# VIC20_HypExp.net
KiCad netlist of a schematic drawn in EAGLE
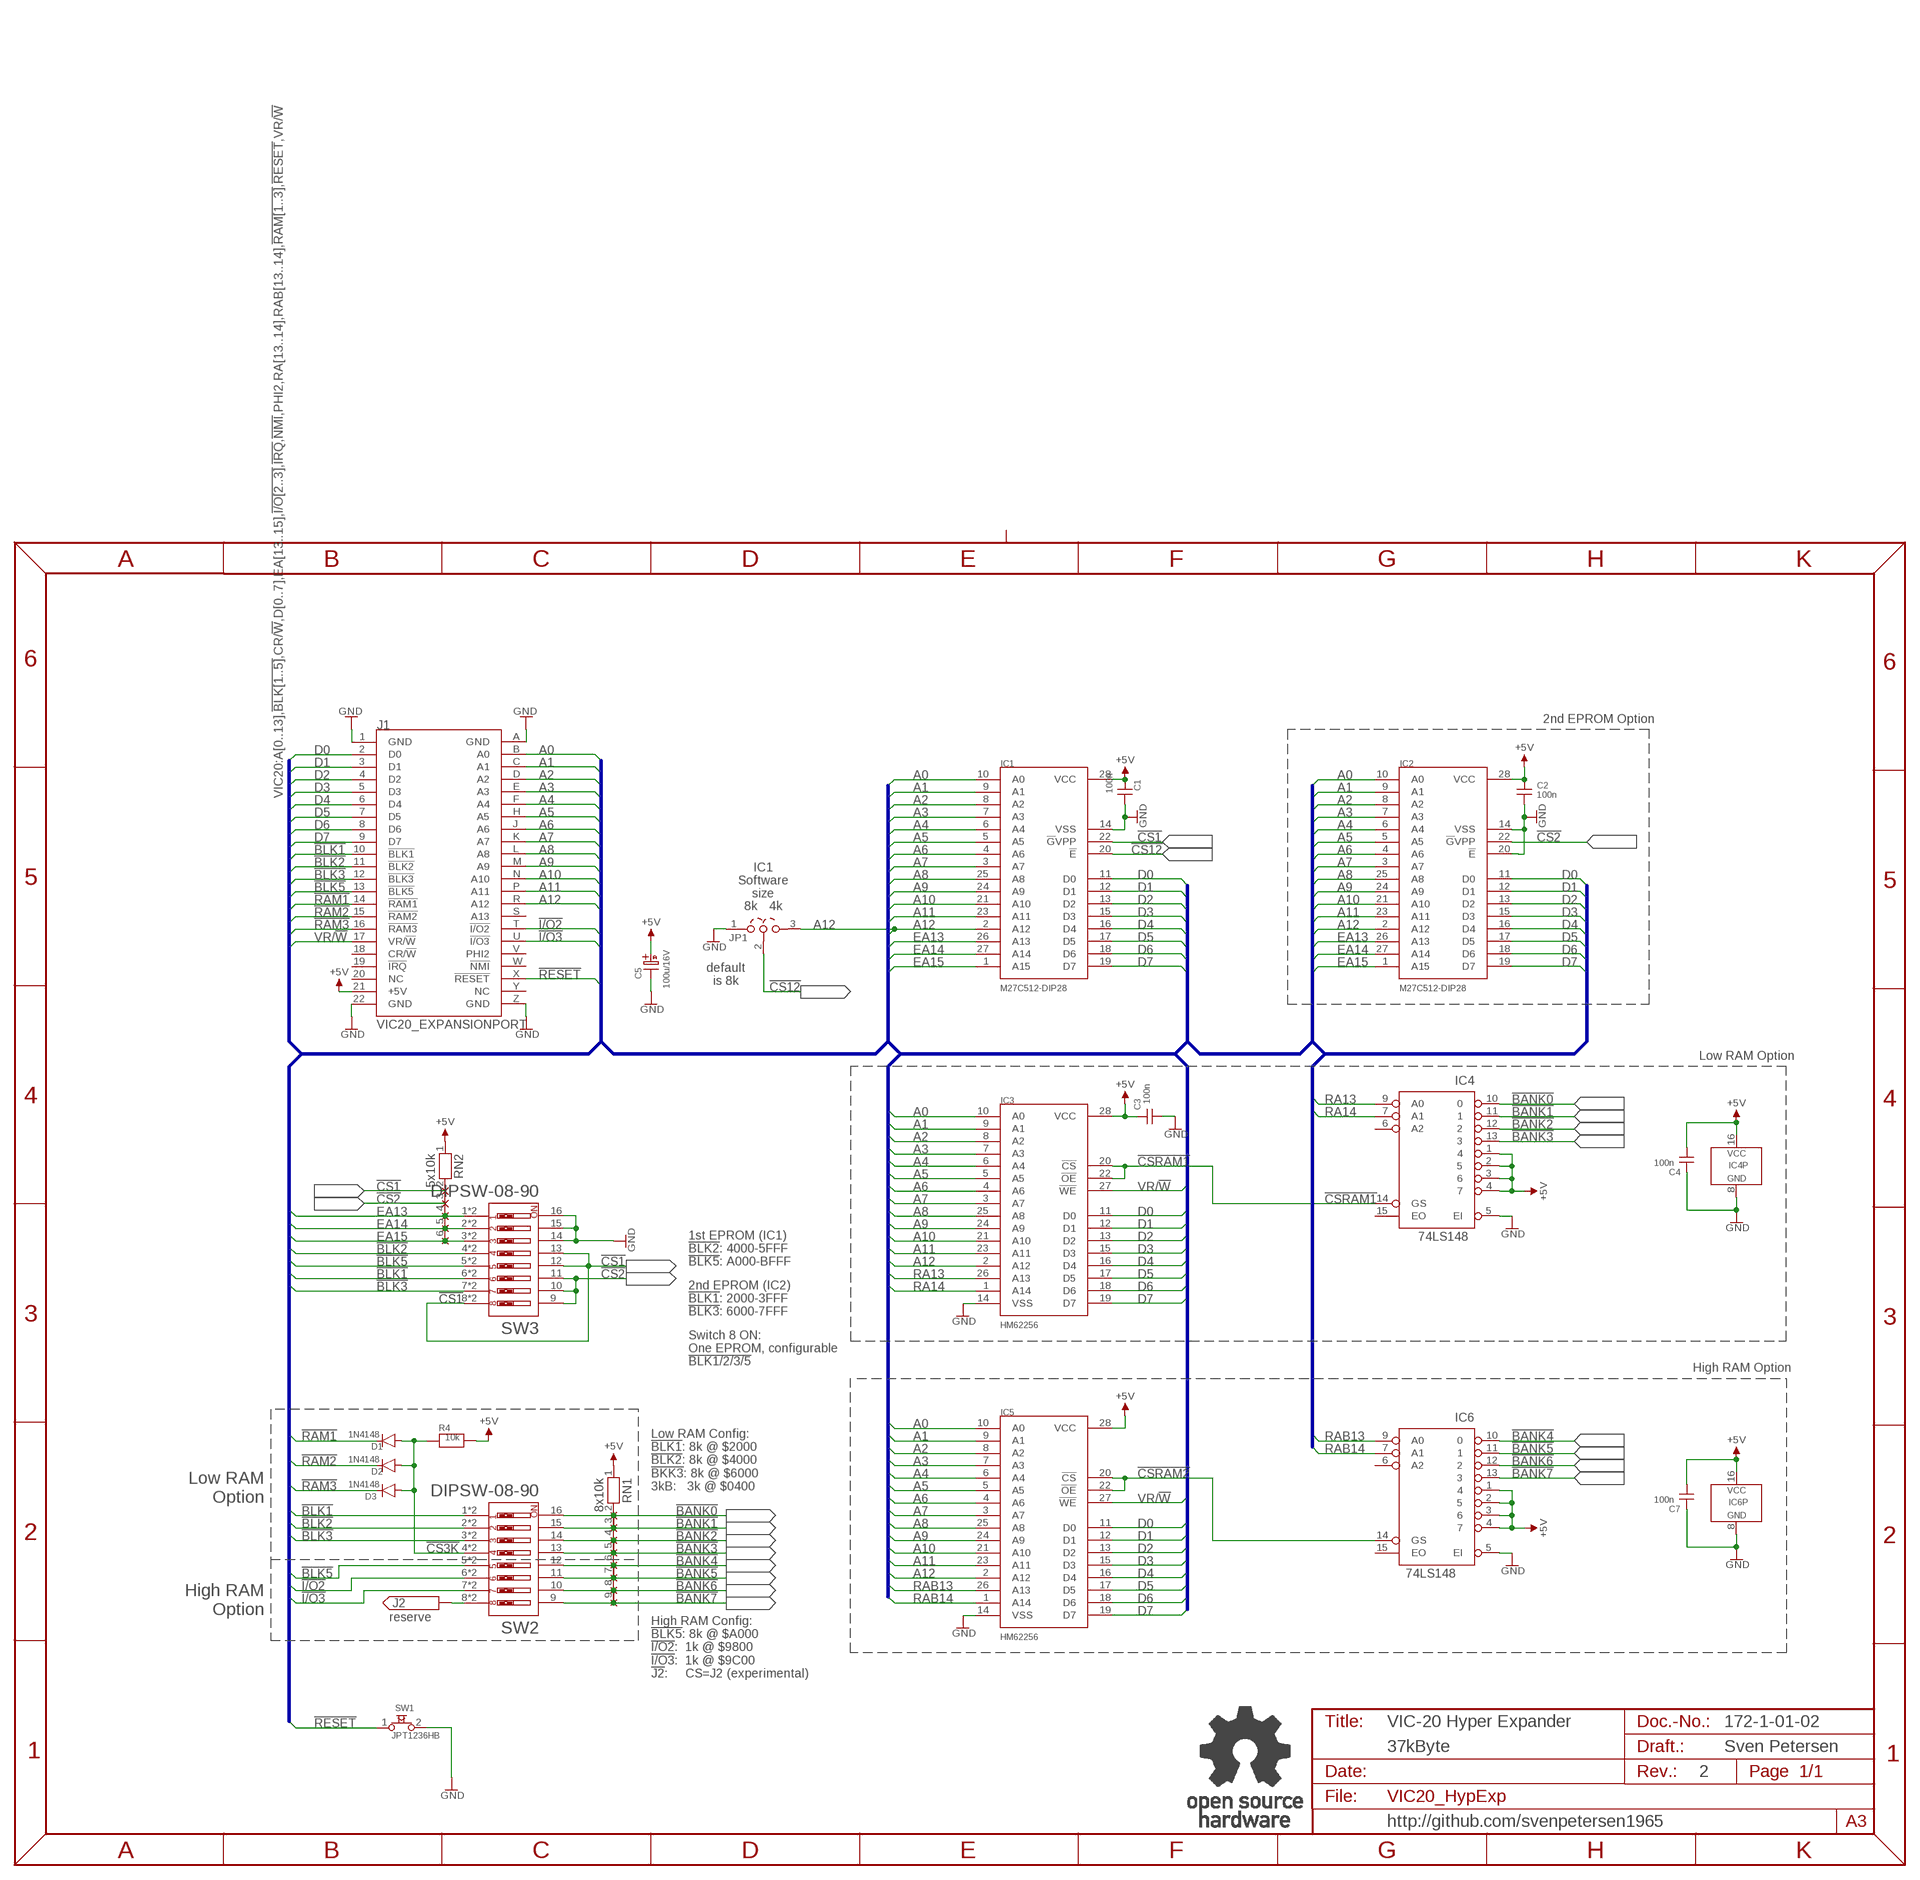
[diagram p0: schematic, sheet 1]

(export (version "E")
  (design (tool "Eeschema 10.0.6"))
  (components
    (comp (ref "C1")
      (value "100n")
      (footprint "eagle-import:C-2,5")
      (libsource (lib "eagle-import") (part "CAP01"))
    )
    (comp (ref "C2")
      (value "100n")
      (footprint "eagle-import:C-2,5")
      (libsource (lib "eagle-import") (part "CAP01"))
    )
    (comp (ref "C3")
      (value "100n")
      (footprint "eagle-import:C-2,5")
      (libsource (lib "eagle-import") (part "CAP01"))
    )
    (comp (ref "C4")
      (value "100n")
      (footprint "eagle-import:C-2,5")
      (libsource (lib "eagle-import") (part "CAP01"))
    )
    (comp (ref "C5")
      (value "100u/16V")
      (footprint "eagle-import:C07_2,5")
      (libsource (lib "eagle-import") (part "C07/2,5"))
    )
    (comp (ref "C7")
      (value "100n")
      (footprint "eagle-import:C-2,5")
      (libsource (lib "eagle-import") (part "CAP01"))
    )
    (comp (ref "D1")
      (value "1N4148")
      (footprint "eagle-import:DO-35_3")
      (libsource (lib "eagle-import") (part "1N41480.3{dblquote}"))
    )
    (comp (ref "D2")
      (value "1N4148")
      (footprint "eagle-import:DO-35_3")
      (libsource (lib "eagle-import") (part "1N41480.3{dblquote}"))
    )
    (comp (ref "D3")
      (value "1N4148")
      (footprint "eagle-import:DO-35_3")
      (libsource (lib "eagle-import") (part "1N41480.3{dblquote}"))
    )
    (comp (ref "IC1")
      (value "M27C512-DIP28")
      (footprint "eagle-import:DIL28-6")
      (libsource (lib "eagle-import") (part "M27C512-DIP28"))
    )
    (comp (ref "IC2")
      (value "M27C512-DIP28")
      (footprint "eagle-import:DIL28-6")
      (libsource (lib "eagle-import") (part "M27C512-DIP28"))
    )
    (comp (ref "IC3")
      (value "HM62256")
      (footprint "eagle-import:DIL28-6")
      (libsource (lib "eagle-import") (part "HM62256"))
    )
    (comp (ref "IC4")
      (value "74LS148")
      (footprint "eagle-import:DIL-16")
      (libsource (lib "eagle-import") (part "74148DIL"))
    )
    (comp (ref "IC5")
      (value "HM62256")
      (footprint "eagle-import:DIL28-6")
      (libsource (lib "eagle-import") (part "HM62256"))
    )
    (comp (ref "IC6")
      (value "74LS148")
      (footprint "eagle-import:DIL-16")
      (libsource (lib "eagle-import") (part "74148DIL"))
    )
    (comp (ref "J1")
      (value "VIC20_EXPANSIONPORT")
      (footprint "eagle-import:VIC20_EXPANSION")
      (libsource (lib "eagle-import") (part "VIC20_EXPANSIONPORT"))
    )
    (comp (ref "J2")
      (value "PINHD-1X1")
      (footprint "eagle-import:1X01")
      (libsource (lib "eagle-import") (part "PINHD-1X1"))
    )
    (comp (ref "JP1")
      (value "COMBI-3P")
      (footprint "eagle-import:COMBI-3P")
      (libsource (lib "eagle-import") (part "COMBI-3P"))
    )
    (comp (ref "R4")
      (value "10k")
      (footprint "eagle-import:R-10")
      (libsource (lib "eagle-import") (part "RES04"))
    )
    (comp (ref "RN1")
      (value "8x10k")
      (footprint "eagle-import:RN-9")
      (libsource (lib "eagle-import") (part "RN08"))
    )
    (comp (ref "RN2")
      (value "5x10k")
      (footprint "eagle-import:RN-6")
      (libsource (lib "eagle-import") (part "RN05"))
    )
    (comp (ref "SW1")
      (value "JPT1236HB")
      (footprint "eagle-import:JTP_1236HB")
      (libsource (lib "eagle-import") (part "JPT1236HB"))
    )
    (comp (ref "SW2")
      (value "DIPSW-08-90")
      (footprint "eagle-import:DIPSW-08-90")
      (libsource (lib "eagle-import") (part "DIPSW-08-90"))
    )
    (comp (ref "SW3")
      (value "DIPSW-08-90")
      (footprint "eagle-import:DIPSW-08-90")
      (libsource (lib "eagle-import") (part "DIPSW-08-90"))
    )
    (comp (ref "U$2")
      (value "OPEN_SOURCE_HW")
      (footprint "eagle-import:OPENHW")
      (libsource (lib "eagle-import") (part "OPEN_SOURCE_HW"))
    )
  )
  (nets
    (net (code "5") (name "+5V") (class "Default")
      (node (ref "C1") (pin "1") (pinfunction "1_1") (pintype "passive"))
      (node (ref "C2") (pin "1") (pinfunction "1_1") (pintype "passive"))
      (node (ref "C3") (pin "2") (pinfunction "2_2") (pintype "passive"))
      (node (ref "C4") (pin "1") (pinfunction "1_1") (pintype "passive"))
      (node (ref "C5") (pin "A") (pinfunction "+_A") (pintype "passive"))
      (node (ref "C7") (pin "1") (pinfunction "1_1") (pintype "passive"))
      (node (ref "IC1") (pin "28") (pinfunction "VCC_28") (pintype "power_in"))
      (node (ref "IC2") (pin "28") (pinfunction "VCC_28") (pintype "power_in"))
      (node (ref "IC3") (pin "28") (pinfunction "VCC_28") (pintype "power_in"))
      (node (ref "IC4") (pin "1") (pinfunction "4_1") (pintype "input"))
      (node (ref "IC4") (pin "16") (pinfunction "VCC_16") (pintype "bidirectional"))
      (node (ref "IC4") (pin "2") (pinfunction "5_2") (pintype "input"))
      (node (ref "IC4") (pin "3") (pinfunction "6_3") (pintype "input"))
      (node (ref "IC4") (pin "4") (pinfunction "7_4") (pintype "input"))
      (node (ref "IC5") (pin "28") (pinfunction "VCC_28") (pintype "power_in"))
      (node (ref "IC6") (pin "1") (pinfunction "4_1") (pintype "input"))
      (node (ref "IC6") (pin "16") (pinfunction "VCC_16") (pintype "bidirectional"))
      (node (ref "IC6") (pin "2") (pinfunction "5_2") (pintype "input"))
      (node (ref "IC6") (pin "3") (pinfunction "6_3") (pintype "input"))
      (node (ref "IC6") (pin "4") (pinfunction "7_4") (pintype "input"))
      (node (ref "J1") (pin "21") (pinfunction "+5V_21") (pintype "power_in"))
      (node (ref "R4") (pin "2") (pinfunction "2_2") (pintype "passive"))
      (node (ref "RN1") (pin "1") (pinfunction "1_1") (pintype "passive"))
      (node (ref "RN2") (pin "1") (pinfunction "1_1") (pintype "passive"))
    )
    (net (code "6") (name "/A0") (class "Default")
      (node (ref "IC1") (pin "10") (pinfunction "A0_10") (pintype "input"))
      (node (ref "IC2") (pin "10") (pinfunction "A0_10") (pintype "input"))
      (node (ref "IC3") (pin "10") (pinfunction "A0_10") (pintype "input"))
      (node (ref "IC5") (pin "10") (pinfunction "A0_10") (pintype "input"))
      (node (ref "J1") (pin "B") (pinfunction "A0_B") (pintype "bidirectional"))
    )
    (net (code "7") (name "/A1") (class "Default")
      (node (ref "IC1") (pin "9") (pinfunction "A1_9") (pintype "input"))
      (node (ref "IC2") (pin "9") (pinfunction "A1_9") (pintype "input"))
      (node (ref "IC3") (pin "9") (pinfunction "A1_9") (pintype "input"))
      (node (ref "IC5") (pin "9") (pinfunction "A1_9") (pintype "input"))
      (node (ref "J1") (pin "C") (pinfunction "A1_C") (pintype "bidirectional"))
    )
    (net (code "8") (name "/A2") (class "Default")
      (node (ref "IC1") (pin "8") (pinfunction "A2_8") (pintype "input"))
      (node (ref "IC2") (pin "8") (pinfunction "A2_8") (pintype "input"))
      (node (ref "IC3") (pin "8") (pinfunction "A2_8") (pintype "input"))
      (node (ref "IC5") (pin "8") (pinfunction "A2_8") (pintype "input"))
      (node (ref "J1") (pin "D") (pinfunction "A2_D") (pintype "bidirectional"))
    )
    (net (code "9") (name "/A3") (class "Default")
      (node (ref "IC1") (pin "7") (pinfunction "A3_7") (pintype "input"))
      (node (ref "IC2") (pin "7") (pinfunction "A3_7") (pintype "input"))
      (node (ref "IC3") (pin "7") (pinfunction "A3_7") (pintype "input"))
      (node (ref "IC5") (pin "7") (pinfunction "A3_7") (pintype "input"))
      (node (ref "J1") (pin "E") (pinfunction "A3_E") (pintype "bidirectional"))
    )
    (net (code "10") (name "/A4") (class "Default")
      (node (ref "IC1") (pin "6") (pinfunction "A4_6") (pintype "input"))
      (node (ref "IC2") (pin "6") (pinfunction "A4_6") (pintype "input"))
      (node (ref "IC3") (pin "6") (pinfunction "A4_6") (pintype "input"))
      (node (ref "IC5") (pin "6") (pinfunction "A4_6") (pintype "input"))
      (node (ref "J1") (pin "F") (pinfunction "A4_F") (pintype "bidirectional"))
    )
    (net (code "11") (name "/A5") (class "Default")
      (node (ref "IC1") (pin "5") (pinfunction "A5_5") (pintype "input"))
      (node (ref "IC2") (pin "5") (pinfunction "A5_5") (pintype "input"))
      (node (ref "IC3") (pin "5") (pinfunction "A5_5") (pintype "input"))
      (node (ref "IC5") (pin "5") (pinfunction "A5_5") (pintype "input"))
      (node (ref "J1") (pin "H") (pinfunction "A5_H") (pintype "bidirectional"))
    )
    (net (code "12") (name "/A6") (class "Default")
      (node (ref "IC1") (pin "4") (pinfunction "A6_4") (pintype "input"))
      (node (ref "IC2") (pin "4") (pinfunction "A6_4") (pintype "input"))
      (node (ref "IC3") (pin "4") (pinfunction "A6_4") (pintype "input"))
      (node (ref "IC5") (pin "4") (pinfunction "A6_4") (pintype "input"))
      (node (ref "J1") (pin "J") (pinfunction "A6_J") (pintype "bidirectional"))
    )
    (net (code "13") (name "/A7") (class "Default")
      (node (ref "IC1") (pin "3") (pinfunction "A7_3") (pintype "input"))
      (node (ref "IC2") (pin "3") (pinfunction "A7_3") (pintype "input"))
      (node (ref "IC3") (pin "3") (pinfunction "A7_3") (pintype "input"))
      (node (ref "IC5") (pin "3") (pinfunction "A7_3") (pintype "input"))
      (node (ref "J1") (pin "K") (pinfunction "A7_K") (pintype "bidirectional"))
    )
    (net (code "14") (name "/A8") (class "Default")
      (node (ref "IC1") (pin "25") (pinfunction "A8_25") (pintype "input"))
      (node (ref "IC2") (pin "25") (pinfunction "A8_25") (pintype "input"))
      (node (ref "IC3") (pin "25") (pinfunction "A8_25") (pintype "input"))
      (node (ref "IC5") (pin "25") (pinfunction "A8_25") (pintype "input"))
      (node (ref "J1") (pin "L") (pinfunction "A8_L") (pintype "bidirectional"))
    )
    (net (code "15") (name "/A9") (class "Default")
      (node (ref "IC1") (pin "24") (pinfunction "A9_24") (pintype "input"))
      (node (ref "IC2") (pin "24") (pinfunction "A9_24") (pintype "input"))
      (node (ref "IC3") (pin "24") (pinfunction "A9_24") (pintype "input"))
      (node (ref "IC5") (pin "24") (pinfunction "A9_24") (pintype "input"))
      (node (ref "J1") (pin "M") (pinfunction "A9_M") (pintype "bidirectional"))
    )
    (net (code "16") (name "/A10") (class "Default")
      (node (ref "IC1") (pin "21") (pinfunction "A10_21") (pintype "input"))
      (node (ref "IC2") (pin "21") (pinfunction "A10_21") (pintype "input"))
      (node (ref "IC3") (pin "21") (pinfunction "A10_21") (pintype "input"))
      (node (ref "IC5") (pin "21") (pinfunction "A10_21") (pintype "input"))
      (node (ref "J1") (pin "N") (pinfunction "A10_N") (pintype "bidirectional"))
    )
    (net (code "17") (name "/A11") (class "Default")
      (node (ref "IC1") (pin "23") (pinfunction "A11_23") (pintype "input"))
      (node (ref "IC2") (pin "23") (pinfunction "A11_23") (pintype "input"))
      (node (ref "IC3") (pin "23") (pinfunction "A11_23") (pintype "input"))
      (node (ref "IC5") (pin "23") (pinfunction "A11_23") (pintype "input"))
      (node (ref "J1") (pin "P") (pinfunction "A11_P") (pintype "bidirectional"))
    )
    (net (code "18") (name "/A12") (class "Default")
      (node (ref "IC1") (pin "2") (pinfunction "A12_2") (pintype "input"))
      (node (ref "IC2") (pin "2") (pinfunction "A12_2") (pintype "input"))
      (node (ref "IC3") (pin "2") (pinfunction "A12_2") (pintype "input"))
      (node (ref "IC5") (pin "2") (pinfunction "A12_2") (pintype "input"))
      (node (ref "J1") (pin "R") (pinfunction "A12_R") (pintype "bidirectional"))
      (node (ref "JP1") (pin "3") (pinfunction "3_3") (pintype "bidirectional"))
    )
    (net (code "19") (name "/D0") (class "Default")
      (node (ref "IC1") (pin "11") (pinfunction "D0_11") (pintype "bidirectional"))
      (node (ref "IC2") (pin "11") (pinfunction "D0_11") (pintype "bidirectional"))
      (node (ref "IC3") (pin "11") (pinfunction "D0_11") (pintype "bidirectional"))
      (node (ref "IC5") (pin "11") (pinfunction "D0_11") (pintype "bidirectional"))
      (node (ref "J1") (pin "2") (pinfunction "D0_2") (pintype "bidirectional"))
    )
    (net (code "20") (name "/D1") (class "Default")
      (node (ref "IC1") (pin "12") (pinfunction "D1_12") (pintype "bidirectional"))
      (node (ref "IC2") (pin "12") (pinfunction "D1_12") (pintype "bidirectional"))
      (node (ref "IC3") (pin "12") (pinfunction "D1_12") (pintype "bidirectional"))
      (node (ref "IC5") (pin "12") (pinfunction "D1_12") (pintype "bidirectional"))
      (node (ref "J1") (pin "3") (pinfunction "D1_3") (pintype "bidirectional"))
    )
    (net (code "21") (name "/D2") (class "Default")
      (node (ref "IC1") (pin "13") (pinfunction "D2_13") (pintype "bidirectional"))
      (node (ref "IC2") (pin "13") (pinfunction "D2_13") (pintype "bidirectional"))
      (node (ref "IC3") (pin "13") (pinfunction "D2_13") (pintype "bidirectional"))
      (node (ref "IC5") (pin "13") (pinfunction "D2_13") (pintype "bidirectional"))
      (node (ref "J1") (pin "4") (pinfunction "D2_4") (pintype "bidirectional"))
    )
    (net (code "22") (name "/D3") (class "Default")
      (node (ref "IC1") (pin "15") (pinfunction "D3_15") (pintype "bidirectional"))
      (node (ref "IC2") (pin "15") (pinfunction "D3_15") (pintype "bidirectional"))
      (node (ref "IC3") (pin "15") (pinfunction "D3_15") (pintype "bidirectional"))
      (node (ref "IC5") (pin "15") (pinfunction "D3_15") (pintype "bidirectional"))
      (node (ref "J1") (pin "5") (pinfunction "D3_5") (pintype "bidirectional"))
    )
    (net (code "23") (name "/D4") (class "Default")
      (node (ref "IC1") (pin "16") (pinfunction "D4_16") (pintype "bidirectional"))
      (node (ref "IC2") (pin "16") (pinfunction "D4_16") (pintype "bidirectional"))
      (node (ref "IC3") (pin "16") (pinfunction "D4_16") (pintype "bidirectional"))
      (node (ref "IC5") (pin "16") (pinfunction "D4_16") (pintype "bidirectional"))
      (node (ref "J1") (pin "6") (pinfunction "D4_6") (pintype "bidirectional"))
    )
    (net (code "24") (name "/D5") (class "Default")
      (node (ref "IC1") (pin "17") (pinfunction "D5_17") (pintype "bidirectional"))
      (node (ref "IC2") (pin "17") (pinfunction "D5_17") (pintype "bidirectional"))
      (node (ref "IC3") (pin "17") (pinfunction "D5_17") (pintype "bidirectional"))
      (node (ref "IC5") (pin "17") (pinfunction "D5_17") (pintype "bidirectional"))
      (node (ref "J1") (pin "7") (pinfunction "D5_7") (pintype "bidirectional"))
    )
    (net (code "25") (name "/D6") (class "Default")
      (node (ref "IC1") (pin "18") (pinfunction "D6_18") (pintype "bidirectional"))
      (node (ref "IC2") (pin "18") (pinfunction "D6_18") (pintype "bidirectional"))
      (node (ref "IC3") (pin "18") (pinfunction "D6_18") (pintype "bidirectional"))
      (node (ref "IC5") (pin "18") (pinfunction "D6_18") (pintype "bidirectional"))
      (node (ref "J1") (pin "8") (pinfunction "D6_8") (pintype "bidirectional"))
    )
    (net (code "26") (name "/D7") (class "Default")
      (node (ref "IC1") (pin "19") (pinfunction "D7_19") (pintype "bidirectional"))
      (node (ref "IC2") (pin "19") (pinfunction "D7_19") (pintype "bidirectional"))
      (node (ref "IC3") (pin "19") (pinfunction "D7_19") (pintype "bidirectional"))
      (node (ref "IC5") (pin "19") (pinfunction "D7_19") (pintype "bidirectional"))
      (node (ref "J1") (pin "9") (pinfunction "D7_9") (pintype "bidirectional"))
    )
    (net (code "27") (name "/EA13") (class "Default")
      (node (ref "IC1") (pin "26") (pinfunction "A13_26") (pintype "input"))
      (node (ref "IC2") (pin "26") (pinfunction "A13_26") (pintype "input"))
      (node (ref "RN2") (pin "4") (pinfunction "4_4") (pintype "passive"))
      (node (ref "SW3") (pin "1") (pinfunction "1_1") (pintype "passive"))
      (node (ref "SW3") (pin "1A") (pinfunction "1_1A") (pintype "passive"))
    )
    (net (code "28") (name "/EA14") (class "Default")
      (node (ref "IC1") (pin "27") (pinfunction "A14_27") (pintype "input"))
      (node (ref "IC2") (pin "27") (pinfunction "A14_27") (pintype "input"))
      (node (ref "RN2") (pin "5") (pinfunction "5_5") (pintype "passive"))
      (node (ref "SW3") (pin "2") (pinfunction "2_2") (pintype "passive"))
      (node (ref "SW3") (pin "2A") (pinfunction "2_2A") (pintype "passive"))
    )
    (net (code "29") (name "/EA15") (class "Default")
      (node (ref "IC1") (pin "1") (pinfunction "A15_1") (pintype "input"))
      (node (ref "IC2") (pin "1") (pinfunction "A15_1") (pintype "input"))
      (node (ref "RN2") (pin "6") (pinfunction "6_6") (pintype "passive"))
      (node (ref "SW3") (pin "3") (pinfunction "3_3") (pintype "passive"))
      (node (ref "SW3") (pin "3A") (pinfunction "3_3A") (pintype "passive"))
    )
    (net (code "30") (name "/NC") (class "Default")
      (node (ref "J1") (pin "20") (pinfunction "NC_20") (pintype "power_in"))
    )
    (net (code "31") (name "/RA13") (class "Default")
      (node (ref "IC3") (pin "26") (pinfunction "A13_26") (pintype "input"))
      (node (ref "IC4") (pin "9") (pinfunction "A0_9") (pintype "output"))
    )
    (net (code "32") (name "/RA14") (class "Default")
      (node (ref "IC3") (pin "1") (pinfunction "A14_1") (pintype "input"))
      (node (ref "IC4") (pin "7") (pinfunction "A1_7") (pintype "output"))
    )
    (net (code "33") (name "/RAB13") (class "Default")
      (node (ref "IC5") (pin "26") (pinfunction "A13_26") (pintype "input"))
      (node (ref "IC6") (pin "9") (pinfunction "A0_9") (pintype "output"))
    )
    (net (code "34") (name "/RAB14") (class "Default")
      (node (ref "IC5") (pin "1") (pinfunction "A14_1") (pintype "input"))
      (node (ref "IC6") (pin "7") (pinfunction "A1_7") (pintype "output"))
    )
    (net (code "35") (name "/VR{slash}~{W}") (class "Default")
      (node (ref "IC3") (pin "27") (pinfunction "~{WE}_27") (pintype "input"))
      (node (ref "IC5") (pin "27") (pinfunction "~{WE}_27") (pintype "input"))
      (node (ref "J1") (pin "17") (pinfunction "VR/~{W}_17") (pintype "output"))
    )
    (net (code "37") (name "/~{BANK0}") (class "Default")
      (node (ref "IC4") (pin "10") (pinfunction "0_10") (pintype "input"))
      (node (ref "RN1") (pin "2") (pinfunction "2_2") (pintype "passive"))
      (node (ref "SW2") (pin "16") (pinfunction "16_16") (pintype "passive"))
    )
    (net (code "38") (name "/~{BANK1}") (class "Default")
      (node (ref "IC4") (pin "11") (pinfunction "1_11") (pintype "input"))
      (node (ref "RN1") (pin "3") (pinfunction "3_3") (pintype "passive"))
      (node (ref "SW2") (pin "15") (pinfunction "15_15") (pintype "passive"))
    )
    (net (code "39") (name "/~{BANK2}") (class "Default")
      (node (ref "IC4") (pin "12") (pinfunction "2_12") (pintype "input"))
      (node (ref "RN1") (pin "4") (pinfunction "4_4") (pintype "passive"))
      (node (ref "SW2") (pin "14") (pinfunction "14_14") (pintype "passive"))
    )
    (net (code "40") (name "/~{BANK3}") (class "Default")
      (node (ref "IC4") (pin "13") (pinfunction "3_13") (pintype "input"))
      (node (ref "RN1") (pin "5") (pinfunction "5_5") (pintype "passive"))
      (node (ref "SW2") (pin "13") (pinfunction "13_13") (pintype "passive"))
    )
    (net (code "41") (name "/~{BANK4}") (class "Default")
      (node (ref "IC6") (pin "10") (pinfunction "0_10") (pintype "input"))
      (node (ref "RN1") (pin "6") (pinfunction "6_6") (pintype "passive"))
      (node (ref "SW2") (pin "12") (pinfunction "12_12") (pintype "passive"))
    )
    (net (code "42") (name "/~{BANK5}") (class "Default")
      (node (ref "IC6") (pin "11") (pinfunction "1_11") (pintype "input"))
      (node (ref "RN1") (pin "7") (pinfunction "7_7") (pintype "passive"))
      (node (ref "SW2") (pin "11") (pinfunction "11_11") (pintype "passive"))
    )
    (net (code "43") (name "/~{BANK6}") (class "Default")
      (node (ref "IC6") (pin "12") (pinfunction "2_12") (pintype "input"))
      (node (ref "RN1") (pin "8") (pinfunction "8_8") (pintype "passive"))
      (node (ref "SW2") (pin "10") (pinfunction "10_10") (pintype "passive"))
    )
    (net (code "44") (name "/~{BANK7}") (class "Default")
      (node (ref "IC6") (pin "13") (pinfunction "3_13") (pintype "input"))
      (node (ref "RN1") (pin "9") (pinfunction "9_9") (pintype "passive"))
      (node (ref "SW2") (pin "9") (pinfunction "9_9") (pintype "passive"))
    )
    (net (code "45") (name "/~{BLK1}") (class "Default")
      (node (ref "J1") (pin "10") (pinfunction "~{BLK1}_10") (pintype "input"))
      (node (ref "SW2") (pin "1") (pinfunction "1_1") (pintype "passive"))
      (node (ref "SW2") (pin "1A") (pinfunction "1_1A") (pintype "passive"))
      (node (ref "SW3") (pin "6") (pinfunction "6_6") (pintype "passive"))
      (node (ref "SW3") (pin "6A") (pinfunction "6_6A") (pintype "passive"))
    )
    (net (code "46") (name "/~{BLK2}") (class "Default")
      (node (ref "J1") (pin "11") (pinfunction "~{BLK2}_11") (pintype "input"))
      (node (ref "SW2") (pin "2") (pinfunction "2_2") (pintype "passive"))
      (node (ref "SW2") (pin "2A") (pinfunction "2_2A") (pintype "passive"))
      (node (ref "SW3") (pin "4") (pinfunction "4_4") (pintype "passive"))
      (node (ref "SW3") (pin "4A") (pinfunction "4_4A") (pintype "passive"))
    )
    (net (code "47") (name "/~{BLK3}") (class "Default")
      (node (ref "J1") (pin "12") (pinfunction "~{BLK3}_12") (pintype "output"))
      (node (ref "SW2") (pin "3") (pinfunction "3_3") (pintype "passive"))
      (node (ref "SW2") (pin "3A") (pinfunction "3_3A") (pintype "passive"))
      (node (ref "SW3") (pin "7") (pinfunction "7_7") (pintype "passive"))
      (node (ref "SW3") (pin "7A") (pinfunction "7_7A") (pintype "passive"))
    )
    (net (code "48") (name "/~{BLK5}") (class "Default")
      (node (ref "J1") (pin "13") (pinfunction "~{BLK5}_13") (pintype "output"))
      (node (ref "SW2") (pin "5") (pinfunction "5_5") (pintype "passive"))
      (node (ref "SW2") (pin "5A") (pinfunction "5_5A") (pintype "passive"))
      (node (ref "SW3") (pin "5") (pinfunction "5_5") (pintype "passive"))
      (node (ref "SW3") (pin "5A") (pinfunction "5_5A") (pintype "passive"))
    )
    (net (code "49") (name "/~{CS1}") (class "Default")
      (node (ref "IC1") (pin "22") (pinfunction "~{G}VPP_22") (pintype "input"))
      (node (ref "RN2") (pin "2") (pinfunction "2_2") (pintype "passive"))
      (node (ref "SW3") (pin "12") (pinfunction "12_12") (pintype "passive"))
      (node (ref "SW3") (pin "13") (pinfunction "13_13") (pintype "passive"))
      (node (ref "SW3") (pin "8") (pinfunction "8_8") (pintype "passive"))
      (node (ref "SW3") (pin "8A") (pinfunction "8_8A") (pintype "passive"))
    )
    (net (code "50") (name "/~{CS2}") (class "Default")
      (node (ref "IC2") (pin "22") (pinfunction "~{G}VPP_22") (pintype "input"))
      (node (ref "RN2") (pin "3") (pinfunction "3_3") (pintype "passive"))
      (node (ref "SW3") (pin "10") (pinfunction "10_10") (pintype "passive"))
      (node (ref "SW3") (pin "11") (pinfunction "11_11") (pintype "passive"))
      (node (ref "SW3") (pin "9") (pinfunction "9_9") (pintype "passive"))
    )
    (net (code "51") (name "/~{CS3K}") (class "Default")
      (node (ref "D1") (pin "A") (pinfunction "A_A") (pintype "passive"))
      (node (ref "D2") (pin "A") (pinfunction "A_A") (pintype "passive"))
      (node (ref "D3") (pin "A") (pinfunction "A_A") (pintype "passive"))
      (node (ref "R4") (pin "1") (pinfunction "1_1") (pintype "passive"))
      (node (ref "SW2") (pin "4") (pinfunction "4_4") (pintype "passive"))
      (node (ref "SW2") (pin "4A") (pinfunction "4_4A") (pintype "passive"))
    )
    (net (code "52") (name "/~{CS12}") (class "Default")
      (node (ref "IC1") (pin "20") (pinfunction "~{E}_20") (pintype "input"))
      (node (ref "JP1") (pin "2") (pinfunction "2_2") (pintype "bidirectional"))
    )
    (net (code "53") (name "/~{CSRAM1}") (class "Default")
      (node (ref "IC3") (pin "20") (pinfunction "~{CS}_20") (pintype "input"))
      (node (ref "IC3") (pin "22") (pinfunction "~{OE}_22") (pintype "input"))
      (node (ref "IC4") (pin "14") (pinfunction "GS_14") (pintype "output"))
    )
    (net (code "54") (name "/~{CSRAM2}") (class "Default")
      (node (ref "IC5") (pin "20") (pinfunction "~{CS}_20") (pintype "input"))
      (node (ref "IC5") (pin "22") (pinfunction "~{OE}_22") (pintype "input"))
      (node (ref "IC6") (pin "14") (pinfunction "GS_14") (pintype "output"))
    )
    (net (code "55") (name "/~{I{slash}O2}") (class "Default")
      (node (ref "J1") (pin "T") (pinfunction "~{I/O2}_T") (pintype "output"))
      (node (ref "SW2") (pin "6") (pinfunction "6_6") (pintype "passive"))
      (node (ref "SW2") (pin "6A") (pinfunction "6_6A") (pintype "passive"))
    )
    (net (code "56") (name "/~{I{slash}O3}") (class "Default")
      (node (ref "J1") (pin "U") (pinfunction "~{I/O3}_U") (pintype "output"))
      (node (ref "SW2") (pin "7") (pinfunction "7_7") (pintype "passive"))
      (node (ref "SW2") (pin "7A") (pinfunction "7_7A") (pintype "passive"))
    )
    (net (code "57") (name "/~{RAM1}") (class "Default")
      (node (ref "D1") (pin "K") (pinfunction "K_K") (pintype "passive"))
      (node (ref "J1") (pin "14") (pinfunction "~{RAM1}_14") (pintype "input"))
    )
    (net (code "58") (name "/~{RAM2}") (class "Default")
      (node (ref "D2") (pin "K") (pinfunction "K_K") (pintype "passive"))
      (node (ref "J1") (pin "15") (pinfunction "~{RAM2}_15") (pintype "output"))
    )
    (net (code "59") (name "/~{RAM3}") (class "Default")
      (node (ref "D3") (pin "K") (pinfunction "K_K") (pintype "passive"))
      (node (ref "J1") (pin "16") (pinfunction "~{RAM3}_16") (pintype "output"))
    )
    (net (code "60") (name "/~{RESET}") (class "Default")
      (node (ref "J1") (pin "X") (pinfunction "~{RESET}_X") (pintype "open_collector"))
      (node (ref "SW1") (pin "1") (pinfunction "1_1") (pintype "passive"))
    )
    (net (code "61") (name "GND") (class "Default")
      (node (ref "C1") (pin "2") (pinfunction "2_2") (pintype "passive"))
      (node (ref "C2") (pin "2") (pinfunction "2_2") (pintype "passive"))
      (node (ref "C3") (pin "1") (pinfunction "1_1") (pintype "passive"))
      (node (ref "C4") (pin "2") (pinfunction "2_2") (pintype "passive"))
      (node (ref "C5") (pin "K") (pinfunction "-_K") (pintype "passive"))
      (node (ref "C7") (pin "2") (pinfunction "2_2") (pintype "passive"))
      (node (ref "IC1") (pin "14") (pinfunction "VSS_14") (pintype "power_in"))
      (node (ref "IC2") (pin "14") (pinfunction "VSS_14") (pintype "power_in"))
      (node (ref "IC2") (pin "20") (pinfunction "~{E}_20") (pintype "input"))
      (node (ref "IC3") (pin "14") (pinfunction "VSS_14") (pintype "power_in"))
      (node (ref "IC4") (pin "5") (pinfunction "EI_5") (pintype "input"))
      (node (ref "IC4") (pin "8") (pinfunction "GND_8") (pintype "bidirectional"))
      (node (ref "IC5") (pin "14") (pinfunction "VSS_14") (pintype "power_in"))
      (node (ref "IC6") (pin "5") (pinfunction "EI_5") (pintype "input"))
      (node (ref "IC6") (pin "8") (pinfunction "GND_8") (pintype "bidirectional"))
      (node (ref "J1") (pin "1") (pinfunction "GND_1") (pintype "power_in"))
      (node (ref "J1") (pin "22") (pinfunction "GND_22") (pintype "power_in"))
      (node (ref "J1") (pin "A") (pinfunction "GND_A") (pintype "power_in"))
      (node (ref "J1") (pin "Z") (pinfunction "GND_Z") (pintype "power_in"))
      (node (ref "JP1") (pin "1") (pinfunction "1_1") (pintype "bidirectional"))
      (node (ref "SW1") (pin "2") (pinfunction "2_2") (pintype "passive"))
      (node (ref "SW3") (pin "14") (pinfunction "14_14") (pintype "passive"))
      (node (ref "SW3") (pin "15") (pinfunction "15_15") (pintype "passive"))
      (node (ref "SW3") (pin "16") (pinfunction "16_16") (pintype "passive"))
    )
    (net (code "62") (name "Net-(J2-Pad1)") (class "Default")
      (node (ref "J2") (pin "1") (pinfunction "1_1") (pintype "passive"))
      (node (ref "SW2") (pin "8") (pinfunction "8_8") (pintype "passive"))
      (node (ref "SW2") (pin "8A") (pinfunction "8_8A") (pintype "passive"))
    )
    (net (code "63") (name "unconnected-(IC4A-A2-Pad6)") (class "Default")
      (node (ref "IC4") (pin "6") (pinfunction "A2_6") (pintype "output"))
    )
    (net (code "64") (name "unconnected-(IC4A-EO-Pad15)") (class "Default")
      (node (ref "IC4") (pin "15") (pinfunction "EO_15") (pintype "output"))
    )
    (net (code "65") (name "unconnected-(IC6A-A2-Pad6)") (class "Default")
      (node (ref "IC6") (pin "6") (pinfunction "A2_6") (pintype "output"))
    )
    (net (code "66") (name "unconnected-(IC6A-EO-Pad15)") (class "Default")
      (node (ref "IC6") (pin "15") (pinfunction "EO_15") (pintype "output"))
    )
    (net (code "67") (name "unconnected-(J1-A13-PadS)") (class "Default")
      (node (ref "J1") (pin "S") (pinfunction "A13_S") (pintype "bidirectional"))
    )
    (net (code "68") (name "unconnected-(J1-CR{slash}~{W}-Pad18)") (class "Default")
      (node (ref "J1") (pin "18") (pinfunction "CR/~{W}_18") (pintype "output"))
    )
    (net (code "69") (name "unconnected-(J1-NC-PadY)") (class "Default")
      (node (ref "J1") (pin "Y") (pinfunction "NC_Y") (pintype "bidirectional"))
    )
    (net (code "70") (name "unconnected-(J1-PHI2-PadV)") (class "Default")
      (node (ref "J1") (pin "V") (pinfunction "PHI2_V") (pintype "bidirectional"))
    )
    (net (code "71") (name "unconnected-(J1-~{IRQ}-Pad19)") (class "Default")
      (node (ref "J1") (pin "19") (pinfunction "~{IRQ}_19") (pintype "input"))
    )
    (net (code "72") (name "unconnected-(J1-~{NMI}-PadW)") (class "Default")
      (node (ref "J1") (pin "W") (pinfunction "~{NMI}_W") (pintype "input"))
    )
  )
)
